# EnsembleTwo.net
KiCad netlist of a schematic drawn in EAGLE
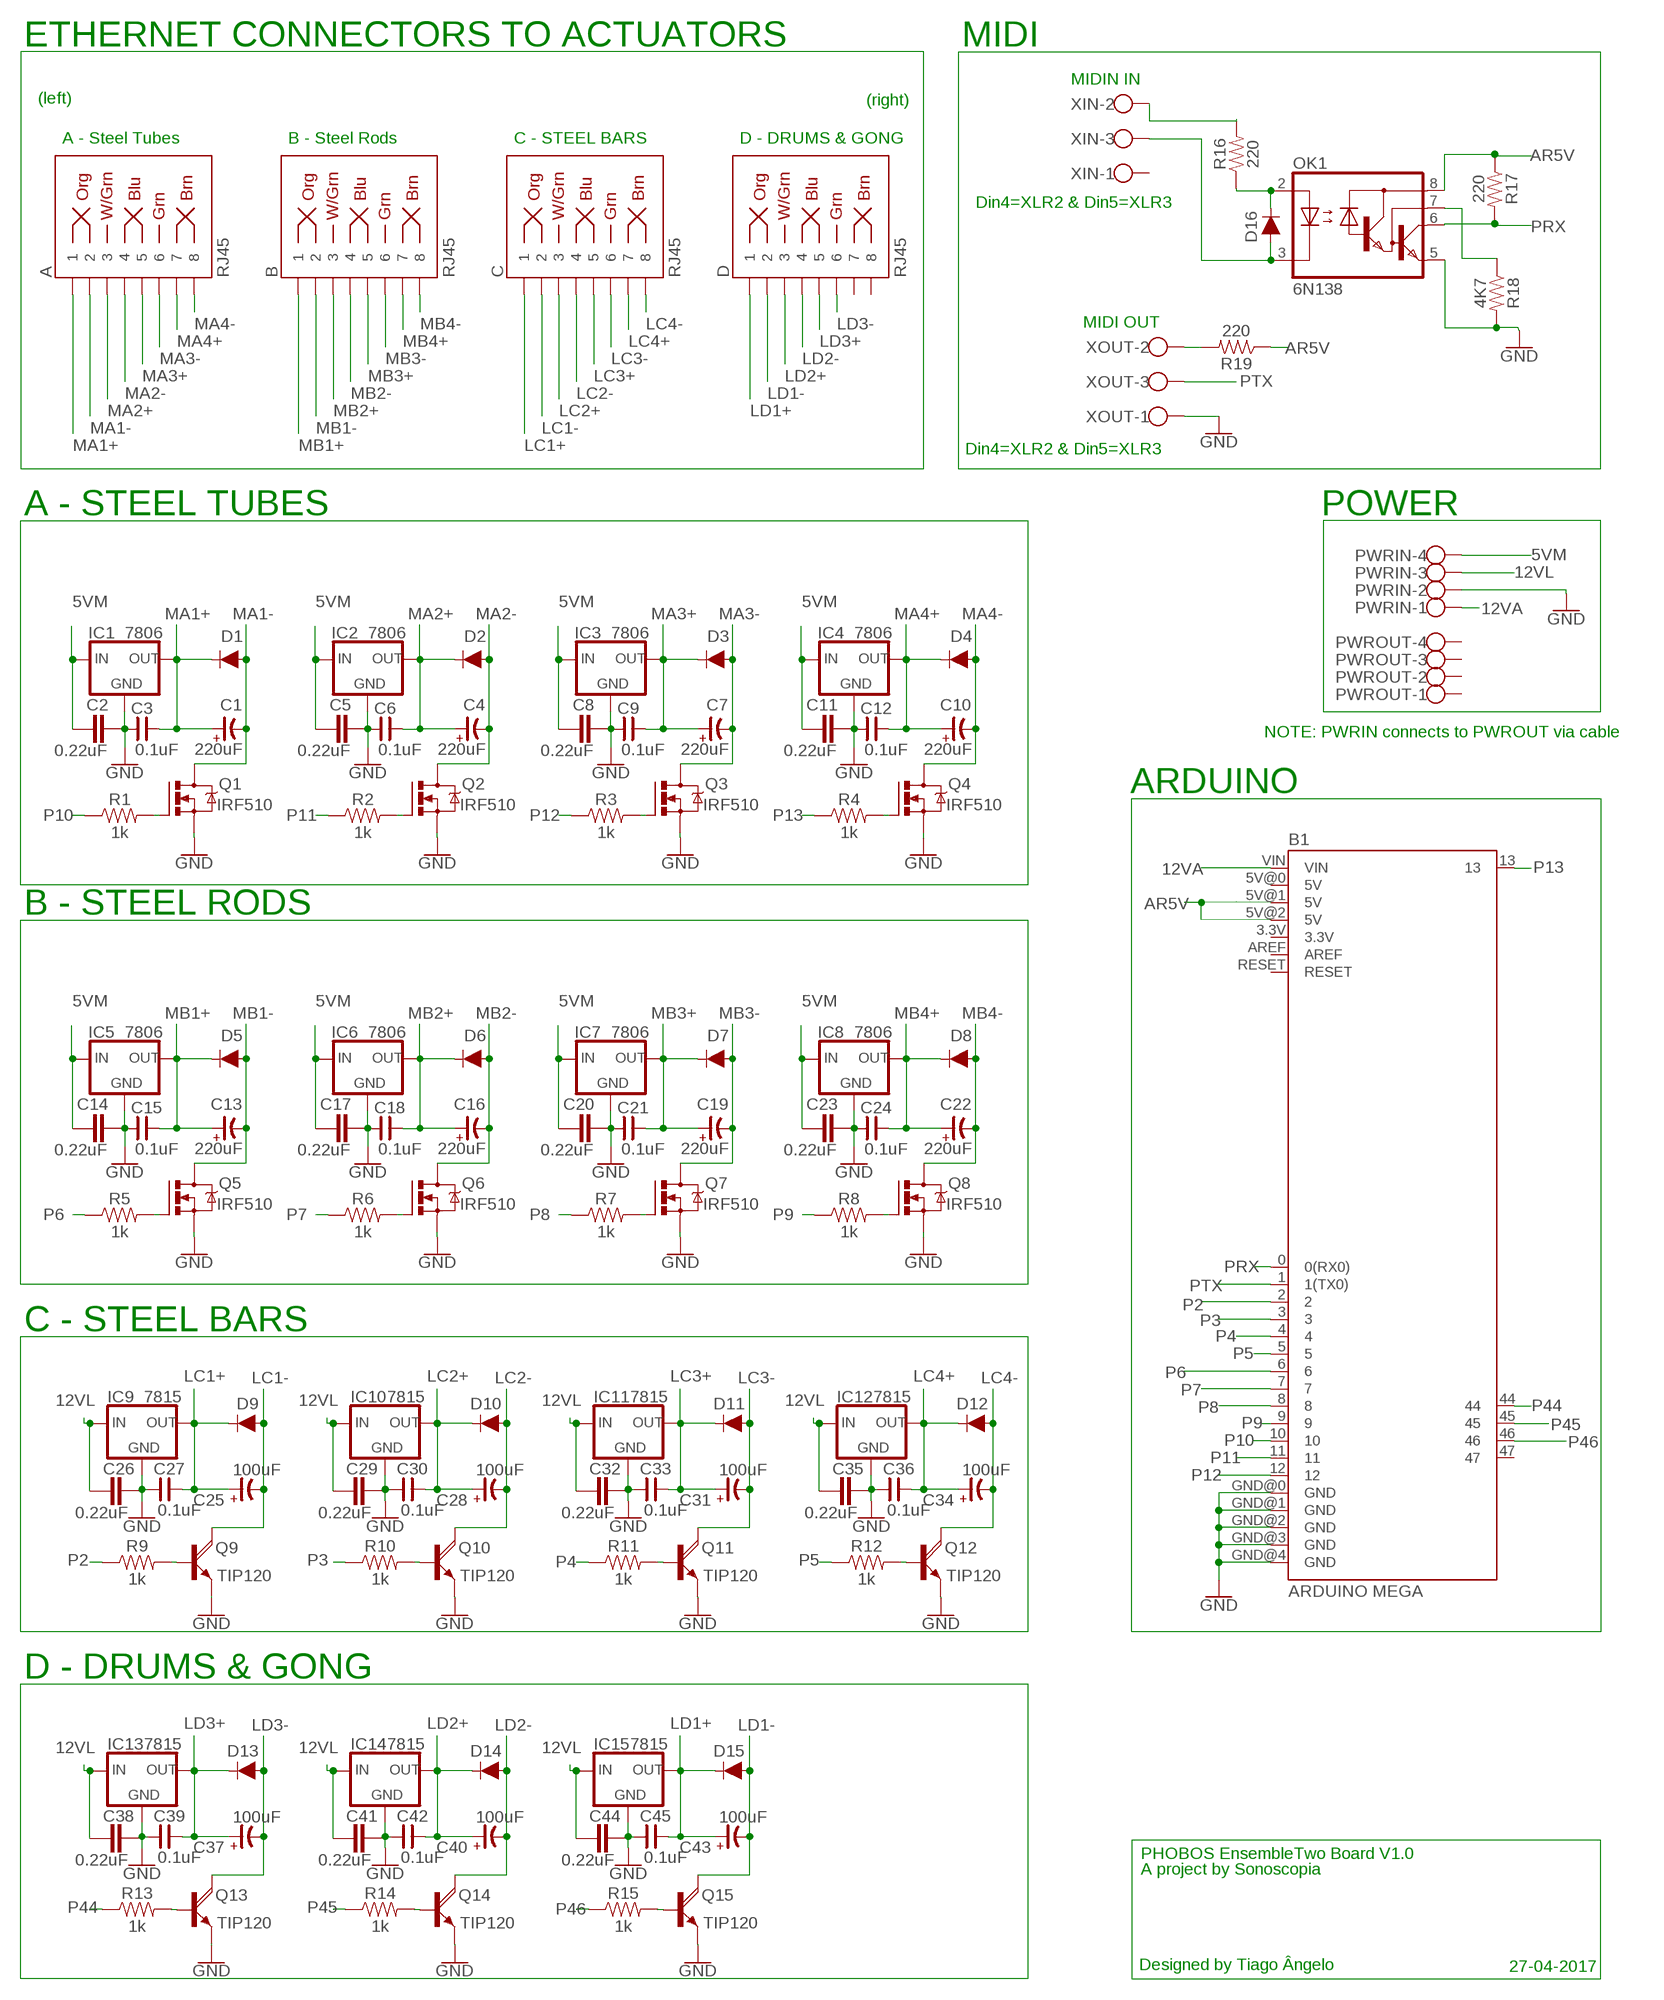
[diagram p0: schematic, sheet 1]

(export (version "E")
  (design (tool "Eeschema 10.0.6"))
  (components
    (comp (ref "A")
      (value "RJ45")
      (footprint "eagle-import:RJ45-8")
      (libsource (lib "eagle-import") (part "RJ45-8"))
    )
    (comp (ref "B")
      (value "RJ45")
      (footprint "eagle-import:RJ45-8")
      (libsource (lib "eagle-import") (part "RJ45-8"))
    )
    (comp (ref "B1")
      (value "ARDUINO MEGA")
      (footprint "eagle-import:ARDUINO_MEGA")
      (libsource (lib "eagle-import") (part "ARDUINO_MEGA_R3FULL"))
    )
    (comp (ref "C")
      (value "RJ45")
      (footprint "eagle-import:RJ45-8")
      (libsource (lib "eagle-import") (part "RJ45-8"))
    )
    (comp (ref "C1")
      (value "220uF")
      (footprint "eagle-import:E-035X080")
      (libsource (lib "eagle-import") (part "CP-E-035X080"))
    )
    (comp (ref "C2")
      (value "0.22uF")
      (footprint "eagle-import:C5B3")
      (libsource (lib "eagle-import") (part "C5/3"))
    )
    (comp (ref "C3")
      (value "0.1uF")
      (footprint "eagle-import:C025-050X025")
      (libsource (lib "eagle-import") (part "CNP-C025-050X025"))
    )
    (comp (ref "C4")
      (value "220uF")
      (footprint "eagle-import:E-035X080")
      (libsource (lib "eagle-import") (part "CP-E-035X080"))
    )
    (comp (ref "C5")
      (value "0.22uF")
      (footprint "eagle-import:C5B3")
      (libsource (lib "eagle-import") (part "C5/3"))
    )
    (comp (ref "C6")
      (value "0.1uF")
      (footprint "eagle-import:C025-050X025")
      (libsource (lib "eagle-import") (part "CNP-C025-050X025"))
    )
    (comp (ref "C7")
      (value "220uF")
      (footprint "eagle-import:E-035X080")
      (libsource (lib "eagle-import") (part "CP-E-035X080"))
    )
    (comp (ref "C8")
      (value "0.22uF")
      (footprint "eagle-import:C5B3")
      (libsource (lib "eagle-import") (part "C5/3"))
    )
    (comp (ref "C9")
      (value "0.1uF")
      (footprint "eagle-import:C025-050X025")
      (libsource (lib "eagle-import") (part "CNP-C025-050X025"))
    )
    (comp (ref "C10")
      (value "220uF")
      (footprint "eagle-import:E-035X080")
      (libsource (lib "eagle-import") (part "CP-E-035X080"))
    )
    (comp (ref "C11")
      (value "0.22uF")
      (footprint "eagle-import:C5B3")
      (libsource (lib "eagle-import") (part "C5/3"))
    )
    (comp (ref "C12")
      (value "0.1uF")
      (footprint "eagle-import:C025-050X025")
      (libsource (lib "eagle-import") (part "CNP-C025-050X025"))
    )
    (comp (ref "C13")
      (value "220uF")
      (footprint "eagle-import:E-035X080")
      (libsource (lib "eagle-import") (part "CP-E-035X080"))
    )
    (comp (ref "C14")
      (value "0.22uF")
      (footprint "eagle-import:C5B3")
      (libsource (lib "eagle-import") (part "C5/3"))
    )
    (comp (ref "C15")
      (value "0.1uF")
      (footprint "eagle-import:C025-050X025")
      (libsource (lib "eagle-import") (part "CNP-C025-050X025"))
    )
    (comp (ref "C16")
      (value "220uF")
      (footprint "eagle-import:E-035X080")
      (libsource (lib "eagle-import") (part "CP-E-035X080"))
    )
    (comp (ref "C17")
      (value "0.22uF")
      (footprint "eagle-import:C5B3")
      (libsource (lib "eagle-import") (part "C5/3"))
    )
    (comp (ref "C18")
      (value "0.1uF")
      (footprint "eagle-import:C025-050X025")
      (libsource (lib "eagle-import") (part "CNP-C025-050X025"))
    )
    (comp (ref "C19")
      (value "220uF")
      (footprint "eagle-import:E-035X080")
      (libsource (lib "eagle-import") (part "CP-E-035X080"))
    )
    (comp (ref "C20")
      (value "0.22uF")
      (footprint "eagle-import:C5B3")
      (libsource (lib "eagle-import") (part "C5/3"))
    )
    (comp (ref "C21")
      (value "0.1uF")
      (footprint "eagle-import:C025-050X025")
      (libsource (lib "eagle-import") (part "CNP-C025-050X025"))
    )
    (comp (ref "C22")
      (value "220uF")
      (footprint "eagle-import:E-035X080")
      (libsource (lib "eagle-import") (part "CP-E-035X080"))
    )
    (comp (ref "C23")
      (value "0.22uF")
      (footprint "eagle-import:C5B3")
      (libsource (lib "eagle-import") (part "C5/3"))
    )
    (comp (ref "C24")
      (value "0.1uF")
      (footprint "eagle-import:C025-050X025")
      (libsource (lib "eagle-import") (part "CNP-C025-050X025"))
    )
    (comp (ref "C25")
      (value "100uF")
      (footprint "eagle-import:E-020X050")
      (libsource (lib "eagle-import") (part "CP-E-020X050"))
    )
    (comp (ref "C26")
      (value "0.22uF")
      (footprint "eagle-import:C5B3")
      (libsource (lib "eagle-import") (part "C5/3"))
    )
    (comp (ref "C27")
      (value "0.1uF")
      (footprint "eagle-import:C025-050X025")
      (libsource (lib "eagle-import") (part "CNP-C025-050X025"))
    )
    (comp (ref "C28")
      (value "100uF")
      (footprint "eagle-import:E-020X050")
      (libsource (lib "eagle-import") (part "CP-E-020X050"))
    )
    (comp (ref "C29")
      (value "0.22uF")
      (footprint "eagle-import:C5B3")
      (libsource (lib "eagle-import") (part "C5/3"))
    )
    (comp (ref "C30")
      (value "0.1uF")
      (footprint "eagle-import:C025-050X025")
      (libsource (lib "eagle-import") (part "CNP-C025-050X025"))
    )
    (comp (ref "C31")
      (value "100uF")
      (footprint "eagle-import:E-020X050")
      (libsource (lib "eagle-import") (part "CP-E-020X050"))
    )
    (comp (ref "C32")
      (value "0.22uF")
      (footprint "eagle-import:C5B3")
      (libsource (lib "eagle-import") (part "C5/3"))
    )
    (comp (ref "C33")
      (value "0.1uF")
      (footprint "eagle-import:C025-050X025")
      (libsource (lib "eagle-import") (part "CNP-C025-050X025"))
    )
    (comp (ref "C34")
      (value "100uF")
      (footprint "eagle-import:E-020X050")
      (libsource (lib "eagle-import") (part "CP-E-020X050"))
    )
    (comp (ref "C35")
      (value "0.22uF")
      (footprint "eagle-import:C5B3")
      (libsource (lib "eagle-import") (part "C5/3"))
    )
    (comp (ref "C36")
      (value "0.1uF")
      (footprint "eagle-import:C025-050X025")
      (libsource (lib "eagle-import") (part "CNP-C025-050X025"))
    )
    (comp (ref "C37")
      (value "100uF")
      (footprint "eagle-import:E-020X050")
      (libsource (lib "eagle-import") (part "CP-E-020X050"))
    )
    (comp (ref "C38")
      (value "0.22uF")
      (footprint "eagle-import:C5B3")
      (libsource (lib "eagle-import") (part "C5/3"))
    )
    (comp (ref "C39")
      (value "0.1uF")
      (footprint "eagle-import:C025-050X025")
      (libsource (lib "eagle-import") (part "CNP-C025-050X025"))
    )
    (comp (ref "C40")
      (value "100uF")
      (footprint "eagle-import:E-020X050")
      (libsource (lib "eagle-import") (part "CP-E-020X050"))
    )
    (comp (ref "C41")
      (value "0.22uF")
      (footprint "eagle-import:C5B3")
      (libsource (lib "eagle-import") (part "C5/3"))
    )
    (comp (ref "C42")
      (value "0.1uF")
      (footprint "eagle-import:C025-050X025")
      (libsource (lib "eagle-import") (part "CNP-C025-050X025"))
    )
    (comp (ref "C43")
      (value "100uF")
      (footprint "eagle-import:E-020X050")
      (libsource (lib "eagle-import") (part "CP-E-020X050"))
    )
    (comp (ref "C44")
      (value "0.22uF")
      (footprint "eagle-import:C5B3")
      (libsource (lib "eagle-import") (part "C5/3"))
    )
    (comp (ref "C45")
      (value "0.1uF")
      (footprint "eagle-import:C025-050X025")
      (libsource (lib "eagle-import") (part "CNP-C025-050X025"))
    )
    (comp (ref "D")
      (value "RJ45")
      (footprint "eagle-import:RJ45-8")
      (libsource (lib "eagle-import") (part "RJ45-8"))
    )
    (comp (ref "D1")
      (value "1A/50V/1.1V")
      (footprint "eagle-import:DIODE-1N4001-KIT")
      (libsource (lib "eagle-import") (part "DIODE-KIT2"))
    )
    (comp (ref "D2")
      (value "1A/50V/1.1V")
      (footprint "eagle-import:DIODE-1N4001-KIT")
      (libsource (lib "eagle-import") (part "DIODE-KIT2"))
    )
    (comp (ref "D3")
      (value "1A/50V/1.1V")
      (footprint "eagle-import:DIODE-1N4001-KIT")
      (libsource (lib "eagle-import") (part "DIODE-KIT2"))
    )
    (comp (ref "D4")
      (value "1A/50V/1.1V")
      (footprint "eagle-import:DIODE-1N4001-KIT")
      (libsource (lib "eagle-import") (part "DIODE-KIT2"))
    )
    (comp (ref "D5")
      (value "1A/50V/1.1V")
      (footprint "eagle-import:DIODE-1N4001-KIT")
      (libsource (lib "eagle-import") (part "DIODE-KIT2"))
    )
    (comp (ref "D6")
      (value "1A/50V/1.1V")
      (footprint "eagle-import:DIODE-1N4001-KIT")
      (libsource (lib "eagle-import") (part "DIODE-KIT2"))
    )
    (comp (ref "D7")
      (value "1A/50V/1.1V")
      (footprint "eagle-import:DIODE-1N4001-KIT")
      (libsource (lib "eagle-import") (part "DIODE-KIT2"))
    )
    (comp (ref "D8")
      (value "1A/50V/1.1V")
      (footprint "eagle-import:DIODE-1N4001-KIT")
      (libsource (lib "eagle-import") (part "DIODE-KIT2"))
    )
    (comp (ref "D9")
      (value "1A/50V/1.1V")
      (footprint "eagle-import:DIODE-1N4001-KIT")
      (libsource (lib "eagle-import") (part "DIODE-KIT2"))
    )
    (comp (ref "D10")
      (value "1A/50V/1.1V")
      (footprint "eagle-import:DIODE-1N4001-KIT")
      (libsource (lib "eagle-import") (part "DIODE-KIT2"))
    )
    (comp (ref "D11")
      (value "1A/50V/1.1V")
      (footprint "eagle-import:DIODE-1N4001-KIT")
      (libsource (lib "eagle-import") (part "DIODE-KIT2"))
    )
    (comp (ref "D12")
      (value "1A/50V/1.1V")
      (footprint "eagle-import:DIODE-1N4001-KIT")
      (libsource (lib "eagle-import") (part "DIODE-KIT2"))
    )
    (comp (ref "D13")
      (value "1A/50V/1.1V")
      (footprint "eagle-import:DIODE-1N4001-KIT")
      (libsource (lib "eagle-import") (part "DIODE-KIT2"))
    )
    (comp (ref "D14")
      (value "1A/50V/1.1V")
      (footprint "eagle-import:DIODE-1N4001-KIT")
      (libsource (lib "eagle-import") (part "DIODE-KIT2"))
    )
    (comp (ref "D15")
      (value "1A/50V/1.1V")
      (footprint "eagle-import:DIODE-1N4001-KIT")
      (libsource (lib "eagle-import") (part "DIODE-KIT2"))
    )
    (comp (ref "D16")
      (value "200mA/100V/1V")
      (footprint "eagle-import:DIODE-1N4148")
      (libsource (lib "eagle-import") (part "DIODE-1N4148"))
    )
    (comp (ref "IC1")
      (value "7806")
      (footprint "eagle-import:78XXS")
      (libsource (lib "eagle-import") (part "78XXS"))
    )
    (comp (ref "IC2")
      (value "7806")
      (footprint "eagle-import:78XXS")
      (libsource (lib "eagle-import") (part "78XXS"))
    )
    (comp (ref "IC3")
      (value "7806")
      (footprint "eagle-import:78XXS")
      (libsource (lib "eagle-import") (part "78XXS"))
    )
    (comp (ref "IC4")
      (value "7806")
      (footprint "eagle-import:78XXS")
      (libsource (lib "eagle-import") (part "78XXS"))
    )
    (comp (ref "IC5")
      (value "7806")
      (footprint "eagle-import:78XXS")
      (libsource (lib "eagle-import") (part "78XXS"))
    )
    (comp (ref "IC6")
      (value "7806")
      (footprint "eagle-import:78XXS")
      (libsource (lib "eagle-import") (part "78XXS"))
    )
    (comp (ref "IC7")
      (value "7806")
      (footprint "eagle-import:78XXS")
      (libsource (lib "eagle-import") (part "78XXS"))
    )
    (comp (ref "IC8")
      (value "7806")
      (footprint "eagle-import:78XXS")
      (libsource (lib "eagle-import") (part "78XXS"))
    )
    (comp (ref "IC9")
      (value "7815")
      (footprint "eagle-import:78XXS")
      (libsource (lib "eagle-import") (part "78XXS"))
    )
    (comp (ref "IC10")
      (value "7815")
      (footprint "eagle-import:78XXS")
      (libsource (lib "eagle-import") (part "78XXS"))
    )
    (comp (ref "IC11")
      (value "7815")
      (footprint "eagle-import:78XXS")
      (libsource (lib "eagle-import") (part "78XXS"))
    )
    (comp (ref "IC12")
      (value "7815")
      (footprint "eagle-import:78XXS")
      (libsource (lib "eagle-import") (part "78XXS"))
    )
    (comp (ref "IC13")
      (value "7815")
      (footprint "eagle-import:78XXS")
      (libsource (lib "eagle-import") (part "78XXS"))
    )
    (comp (ref "IC14")
      (value "7815")
      (footprint "eagle-import:78XXS")
      (libsource (lib "eagle-import") (part "78XXS"))
    )
    (comp (ref "IC15")
      (value "7815")
      (footprint "eagle-import:78XXS")
      (libsource (lib "eagle-import") (part "78XXS"))
    )
    (comp (ref "OK1")
      (value "6N138")
      (footprint "eagle-import:DIL08")
      (fields (field (name "MF") "VISHAY/TELEFUNKEN"))
      (libsource (lib "eagle-import") (part "6N138"))
    )
    (comp (ref "PWRIN")
      (value "W237-4")
      (footprint "eagle-import:W237-4")
      (libsource (lib "eagle-import") (part "W237-4"))
    )
    (comp (ref "PWROUT")
      (value "W237-4")
      (footprint "eagle-import:W237-4")
      (libsource (lib "eagle-import") (part "W237-4"))
    )
    (comp (ref "Q1")
      (value "IRF510")
      (footprint "eagle-import:TO220BV")
      (libsource (lib "eagle-import") (part "IRF520"))
    )
    (comp (ref "Q2")
      (value "IRF510")
      (footprint "eagle-import:TO220BV")
      (libsource (lib "eagle-import") (part "IRF520"))
    )
    (comp (ref "Q3")
      (value "IRF510")
      (footprint "eagle-import:TO220BV")
      (libsource (lib "eagle-import") (part "IRF520"))
    )
    (comp (ref "Q4")
      (value "IRF510")
      (footprint "eagle-import:TO220BV")
      (libsource (lib "eagle-import") (part "IRF520"))
    )
    (comp (ref "Q5")
      (value "IRF510")
      (footprint "eagle-import:TO220BV")
      (libsource (lib "eagle-import") (part "IRF520"))
    )
    (comp (ref "Q6")
      (value "IRF510")
      (footprint "eagle-import:TO220BV")
      (libsource (lib "eagle-import") (part "IRF520"))
    )
    (comp (ref "Q7")
      (value "IRF510")
      (footprint "eagle-import:TO220BV")
      (libsource (lib "eagle-import") (part "IRF520"))
    )
    (comp (ref "Q8")
      (value "IRF510")
      (footprint "eagle-import:TO220BV")
      (libsource (lib "eagle-import") (part "IRF520"))
    )
    (comp (ref "Q9")
      (value "TIP120")
      (footprint "eagle-import:TO220AV")
      (libsource (lib "eagle-import") (part "TIP120V"))
    )
    (comp (ref "Q10")
      (value "TIP120")
      (footprint "eagle-import:TO220AV")
      (libsource (lib "eagle-import") (part "TIP120V"))
    )
    (comp (ref "Q11")
      (value "TIP120")
      (footprint "eagle-import:TO220AV")
      (libsource (lib "eagle-import") (part "TIP120V"))
    )
    (comp (ref "Q12")
      (value "TIP120")
      (footprint "eagle-import:TO220AV")
      (libsource (lib "eagle-import") (part "TIP120V"))
    )
    (comp (ref "Q13")
      (value "TIP120")
      (footprint "eagle-import:TO220AV")
      (libsource (lib "eagle-import") (part "TIP120V"))
    )
    (comp (ref "Q14")
      (value "TIP120")
      (footprint "eagle-import:TO220AV")
      (libsource (lib "eagle-import") (part "TIP120V"))
    )
    (comp (ref "Q15")
      (value "TIP120")
      (footprint "eagle-import:TO220AV")
      (libsource (lib "eagle-import") (part "TIP120V"))
    )
    (comp (ref "R1")
      (value "1k")
      (footprint "eagle-import:AXIAL-0.1")
      (libsource (lib "eagle-import") (part "1KOHM-VERT-1/4W-1%"))
    )
    (comp (ref "R2")
      (value "1k")
      (footprint "eagle-import:AXIAL-0.1")
      (libsource (lib "eagle-import") (part "1KOHM-VERT-1/4W-1%"))
    )
    (comp (ref "R3")
      (value "1k")
      (footprint "eagle-import:AXIAL-0.1")
      (libsource (lib "eagle-import") (part "1KOHM-VERT-1/4W-1%"))
    )
    (comp (ref "R4")
      (value "1k")
      (footprint "eagle-import:AXIAL-0.1")
      (libsource (lib "eagle-import") (part "1KOHM-VERT-1/4W-1%"))
    )
    (comp (ref "R5")
      (value "1k")
      (footprint "eagle-import:AXIAL-0.1")
      (libsource (lib "eagle-import") (part "1KOHM-VERT-1/4W-1%"))
    )
    (comp (ref "R6")
      (value "1k")
      (footprint "eagle-import:AXIAL-0.1")
      (libsource (lib "eagle-import") (part "1KOHM-VERT-1/4W-1%"))
    )
    (comp (ref "R7")
      (value "1k")
      (footprint "eagle-import:AXIAL-0.1")
      (libsource (lib "eagle-import") (part "1KOHM-VERT-1/4W-1%"))
    )
    (comp (ref "R8")
      (value "1k")
      (footprint "eagle-import:AXIAL-0.1")
      (libsource (lib "eagle-import") (part "1KOHM-VERT-1/4W-1%"))
    )
    (comp (ref "R9")
      (value "1k")
      (footprint "eagle-import:AXIAL-0.1")
      (libsource (lib "eagle-import") (part "1KOHM-VERT-1/4W-1%"))
    )
    (comp (ref "R10")
      (value "1k")
      (footprint "eagle-import:AXIAL-0.1")
      (libsource (lib "eagle-import") (part "1KOHM-VERT-1/4W-1%"))
    )
    (comp (ref "R11")
      (value "1k")
      (footprint "eagle-import:AXIAL-0.1")
      (libsource (lib "eagle-import") (part "1KOHM-VERT-1/4W-1%"))
    )
    (comp (ref "R12")
      (value "1k")
      (footprint "eagle-import:AXIAL-0.1")
      (libsource (lib "eagle-import") (part "1KOHM-VERT-1/4W-1%"))
    )
    (comp (ref "R13")
      (value "1k")
      (footprint "eagle-import:AXIAL-0.1")
      (libsource (lib "eagle-import") (part "1KOHM-VERT-1/4W-1%"))
    )
    (comp (ref "R14")
      (value "1k")
      (footprint "eagle-import:AXIAL-0.1")
      (libsource (lib "eagle-import") (part "1KOHM-VERT-1/4W-1%"))
    )
    (comp (ref "R15")
      (value "1k")
      (footprint "eagle-import:AXIAL-0.1")
      (libsource (lib "eagle-import") (part "1KOHM-VERT-1/4W-1%"))
    )
    (comp (ref "R16")
      (value "220")
      (footprint "eagle-import:AXIAL-0.3")
      (libsource (lib "eagle-import") (part "1KOHM-HORIZ-1/4W-5%"))
    )
    (comp (ref "R17")
      (value "220")
      (footprint "eagle-import:AXIAL-0.3")
      (libsource (lib "eagle-import") (part "1KOHM-HORIZ-1/4W-5%"))
    )
    (comp (ref "R18")
      (value "4K7")
      (footprint "eagle-import:AXIAL-0.3")
      (libsource (lib "eagle-import") (part "1KOHM-HORIZ-1/4W-5%"))
    )
    (comp (ref "R19")
      (value "220")
      (footprint "eagle-import:AXIAL-0.3")
      (libsource (lib "eagle-import") (part "1KOHM-HORIZ-1/4W-5%"))
    )
    (comp (ref "XIN")
      (value "W237-103")
      (footprint "eagle-import:W237-103")
      (fields (field (name "MPN") "237-103"))
      (libsource (lib "eagle-import") (part "W237-103"))
    )
    (comp (ref "XOUT")
      (value "W237-103")
      (footprint "eagle-import:W237-103")
      (fields (field (name "MPN") "237-103"))
      (libsource (lib "eagle-import") (part "W237-103"))
    )
  )
  (nets
    (net (code "1") (name "/5VM") (class "Default")
      (node (ref "C11") (pin "1") (pinfunction "1_1") (pintype "passive"))
      (node (ref "C14") (pin "1") (pinfunction "1_1") (pintype "passive"))
      (node (ref "C17") (pin "1") (pinfunction "1_1") (pintype "passive"))
      (node (ref "C2") (pin "1") (pinfunction "1_1") (pintype "passive"))
      (node (ref "C20") (pin "1") (pinfunction "1_1") (pintype "passive"))
      (node (ref "C23") (pin "1") (pinfunction "1_1") (pintype "passive"))
      (node (ref "C5") (pin "1") (pinfunction "1_1") (pintype "passive"))
      (node (ref "C8") (pin "1") (pinfunction "1_1") (pintype "passive"))
      (node (ref "IC1") (pin "IN") (pinfunction "IN_IN") (pintype "input"))
      (node (ref "IC2") (pin "IN") (pinfunction "IN_IN") (pintype "input"))
      (node (ref "IC3") (pin "IN") (pinfunction "IN_IN") (pintype "input"))
      (node (ref "IC4") (pin "IN") (pinfunction "IN_IN") (pintype "input"))
      (node (ref "IC5") (pin "IN") (pinfunction "IN_IN") (pintype "input"))
      (node (ref "IC6") (pin "IN") (pinfunction "IN_IN") (pintype "input"))
      (node (ref "IC7") (pin "IN") (pinfunction "IN_IN") (pintype "input"))
      (node (ref "IC8") (pin "IN") (pinfunction "IN_IN") (pintype "input"))
      (node (ref "PWRIN") (pin "4") (pinfunction "KL_4") (pintype "passive"))
    )
    (net (code "2") (name "/12VA") (class "Default")
      (node (ref "B1") (pin "VIN") (pinfunction "VIN_VIN") (pintype "bidirectional"))
      (node (ref "PWRIN") (pin "1") (pinfunction "KL_1") (pintype "passive"))
    )
    (net (code "3") (name "/12VL") (class "Default")
      (node (ref "C26") (pin "1") (pinfunction "1_1") (pintype "passive"))
      (node (ref "C29") (pin "1") (pinfunction "1_1") (pintype "passive"))
      (node (ref "C32") (pin "1") (pinfunction "1_1") (pintype "passive"))
      (node (ref "C35") (pin "1") (pinfunction "1_1") (pintype "passive"))
      (node (ref "C38") (pin "1") (pinfunction "1_1") (pintype "passive"))
      (node (ref "C41") (pin "1") (pinfunction "1_1") (pintype "passive"))
      (node (ref "C44") (pin "1") (pinfunction "1_1") (pintype "passive"))
      (node (ref "IC10") (pin "IN") (pinfunction "IN_IN") (pintype "input"))
      (node (ref "IC11") (pin "IN") (pinfunction "IN_IN") (pintype "input"))
      (node (ref "IC12") (pin "IN") (pinfunction "IN_IN") (pintype "input"))
      (node (ref "IC13") (pin "IN") (pinfunction "IN_IN") (pintype "input"))
      (node (ref "IC14") (pin "IN") (pinfunction "IN_IN") (pintype "input"))
      (node (ref "IC15") (pin "IN") (pinfunction "IN_IN") (pintype "input"))
      (node (ref "IC9") (pin "IN") (pinfunction "IN_IN") (pintype "input"))
      (node (ref "PWRIN") (pin "3") (pinfunction "KL_3") (pintype "passive"))
    )
    (net (code "4") (name "/AR5V") (class "Default")
      (node (ref "B1") (pin "5V@1") (pinfunction "5V_5V@1") (pintype "bidirectional"))
      (node (ref "B1") (pin "5V@2") (pinfunction "5V_5V@2") (pintype "bidirectional"))
      (node (ref "OK1") (pin "8") (pinfunction "VCC_8") (pintype "passive"))
      (node (ref "R17") (pin "P$1") (pinfunction "1_P$1") (pintype "passive"))
      (node (ref "R19") (pin "P$1") (pinfunction "1_P$1") (pintype "passive"))
    )
    (net (code "5") (name "/LC1+") (class "Default")
      (node (ref "C") (pin "1") (pinfunction "1_1") (pintype "bidirectional"))
      (node (ref "C25") (pin "+") (pinfunction "+_+") (pintype "passive"))
      (node (ref "C27") (pin "2") (pinfunction "2_2") (pintype "passive"))
      (node (ref "D9") (pin "C") (pinfunction "C_C") (pintype "passive"))
      (node (ref "IC9") (pin "OUT") (pinfunction "OUT_OUT") (pintype "passive"))
    )
    (net (code "6") (name "/LC1-") (class "Default")
      (node (ref "C") (pin "2") (pinfunction "2_2") (pintype "bidirectional"))
      (node (ref "C25") (pin "-") (pinfunction "-_-") (pintype "passive"))
      (node (ref "D9") (pin "A") (pinfunction "A_A") (pintype "passive"))
      (node (ref "Q9") (pin "C") (pinfunction "C_C") (pintype "passive"))
    )
    (net (code "7") (name "/LC2+") (class "Default")
      (node (ref "C") (pin "3") (pinfunction "3_3") (pintype "bidirectional"))
      (node (ref "C28") (pin "+") (pinfunction "+_+") (pintype "passive"))
      (node (ref "C30") (pin "2") (pinfunction "2_2") (pintype "passive"))
      (node (ref "D10") (pin "C") (pinfunction "C_C") (pintype "passive"))
      (node (ref "IC10") (pin "OUT") (pinfunction "OUT_OUT") (pintype "passive"))
    )
    (net (code "8") (name "/LC2-") (class "Default")
      (node (ref "C") (pin "4") (pinfunction "4_4") (pintype "bidirectional"))
      (node (ref "C28") (pin "-") (pinfunction "-_-") (pintype "passive"))
      (node (ref "D10") (pin "A") (pinfunction "A_A") (pintype "passive"))
      (node (ref "Q10") (pin "C") (pinfunction "C_C") (pintype "passive"))
    )
    (net (code "9") (name "/LC3+") (class "Default")
      (node (ref "C") (pin "5") (pinfunction "5_5") (pintype "bidirectional"))
      (node (ref "C31") (pin "+") (pinfunction "+_+") (pintype "passive"))
      (node (ref "C33") (pin "2") (pinfunction "2_2") (pintype "passive"))
      (node (ref "D11") (pin "C") (pinfunction "C_C") (pintype "passive"))
      (node (ref "IC11") (pin "OUT") (pinfunction "OUT_OUT") (pintype "passive"))
    )
    (net (code "10") (name "/LC3-") (class "Default")
      (node (ref "C") (pin "6") (pinfunction "6_6") (pintype "bidirectional"))
      (node (ref "C31") (pin "-") (pinfunction "-_-") (pintype "passive"))
      (node (ref "D11") (pin "A") (pinfunction "A_A") (pintype "passive"))
      (node (ref "Q11") (pin "C") (pinfunction "C_C") (pintype "passive"))
    )
    (net (code "11") (name "/LC4+") (class "Default")
      (node (ref "C") (pin "7") (pinfunction "7_7") (pintype "bidirectional"))
      (node (ref "C34") (pin "+") (pinfunction "+_+") (pintype "passive"))
      (node (ref "C36") (pin "2") (pinfunction "2_2") (pintype "passive"))
      (node (ref "D12") (pin "C") (pinfunction "C_C") (pintype "passive"))
      (node (ref "IC12") (pin "OUT") (pinfunction "OUT_OUT") (pintype "passive"))
    )
    (net (code "12") (name "/LC4-") (class "Default")
      (node (ref "C") (pin "8") (pinfunction "8_8") (pintype "bidirectional"))
      (node (ref "C34") (pin "-") (pinfunction "-_-") (pintype "passive"))
      (node (ref "D12") (pin "A") (pinfunction "A_A") (pintype "passive"))
      (node (ref "Q12") (pin "C") (pinfunction "C_C") (pintype "passive"))
    )
    (net (code "13") (name "/LD1+") (class "Default")
      (node (ref "C43") (pin "+") (pinfunction "+_+") (pintype "passive"))
      (node (ref "C45") (pin "2") (pinfunction "2_2") (pintype "passive"))
      (node (ref "D") (pin "1") (pinfunction "1_1") (pintype "bidirectional"))
      (node (ref "D15") (pin "C") (pinfunction "C_C") (pintype "passive"))
      (node (ref "IC15") (pin "OUT") (pinfunction "OUT_OUT") (pintype "passive"))
    )
    (net (code "14") (name "/LD1-") (class "Default")
      (node (ref "C43") (pin "-") (pinfunction "-_-") (pintype "passive"))
      (node (ref "D") (pin "2") (pinfunction "2_2") (pintype "bidirectional"))
      (node (ref "D15") (pin "A") (pinfunction "A_A") (pintype "passive"))
      (node (ref "Q15") (pin "C") (pinfunction "C_C") (pintype "passive"))
    )
    (net (code "15") (name "/LD2+") (class "Default")
      (node (ref "C40") (pin "+") (pinfunction "+_+") (pintype "passive"))
      (node (ref "C42") (pin "2") (pinfunction "2_2") (pintype "passive"))
      (node (ref "D") (pin "3") (pinfunction "3_3") (pintype "bidirectional"))
      (node (ref "D14") (pin "C") (pinfunction "C_C") (pintype "passive"))
      (node (ref "IC14") (pin "OUT") (pinfunction "OUT_OUT") (pintype "passive"))
    )
    (net (code "16") (name "/LD2-") (class "Default")
      (node (ref "C40") (pin "-") (pinfunction "-_-") (pintype "passive"))
      (node (ref "D") (pin "4") (pinfunction "4_4") (pintype "bidirectional"))
      (node (ref "D14") (pin "A") (pinfunction "A_A") (pintype "passive"))
      (node (ref "Q14") (pin "C") (pinfunction "C_C") (pintype "passive"))
    )
    (net (code "17") (name "/LD3+") (class "Default")
      (node (ref "C37") (pin "+") (pinfunction "+_+") (pintype "passive"))
      (node (ref "C39") (pin "2") (pinfunction "2_2") (pintype "passive"))
      (node (ref "D") (pin "5") (pinfunction "5_5") (pintype "bidirectional"))
      (node (ref "D13") (pin "C") (pinfunction "C_C") (pintype "passive"))
      (node (ref "IC13") (pin "OUT") (pinfunction "OUT_OUT") (pintype "passive"))
    )
    (net (code "18") (name "/LD3-") (class "Default")
      (node (ref "C37") (pin "-") (pinfunction "-_-") (pintype "passive"))
      (node (ref "D") (pin "6") (pinfunction "6_6") (pintype "bidirectional"))
      (node (ref "D13") (pin "A") (pinfunction "A_A") (pintype "passive"))
      (node (ref "Q13") (pin "C") (pinfunction "C_C") (pintype "passive"))
    )
    (net (code "19") (name "/MA1+") (class "Default")
      (node (ref "A") (pin "1") (pinfunction "1_1") (pintype "bidirectional"))
      (node (ref "C1") (pin "+") (pinfunction "+_+") (pintype "passive"))
      (node (ref "C3") (pin "2") (pinfunction "2_2") (pintype "passive"))
      (node (ref "D1") (pin "C") (pinfunction "C_C") (pintype "passive"))
      (node (ref "IC1") (pin "OUT") (pinfunction "OUT_OUT") (pintype "passive"))
    )
    (net (code "20") (name "/MA1-") (class "Default")
      (node (ref "A") (pin "2") (pinfunction "2_2") (pintype "bidirectional"))
      (node (ref "C1") (pin "-") (pinfunction "-_-") (pintype "passive"))
      (node (ref "D1") (pin "A") (pinfunction "A_A") (pintype "passive"))
      (node (ref "Q1") (pin "D") (pinfunction "D_D") (pintype "passive"))
    )
    (net (code "21") (name "/MA2+") (class "Default")
      (node (ref "A") (pin "3") (pinfunction "3_3") (pintype "bidirectional"))
      (node (ref "C4") (pin "+") (pinfunction "+_+") (pintype "passive"))
      (node (ref "C6") (pin "2") (pinfunction "2_2") (pintype "passive"))
      (node (ref "D2") (pin "C") (pinfunction "C_C") (pintype "passive"))
      (node (ref "IC2") (pin "OUT") (pinfunction "OUT_OUT") (pintype "passive"))
    )
    (net (code "22") (name "/MA2-") (class "Default")
      (node (ref "A") (pin "4") (pinfunction "4_4") (pintype "bidirectional"))
      (node (ref "C4") (pin "-") (pinfunction "-_-") (pintype "passive"))
      (node (ref "D2") (pin "A") (pinfunction "A_A") (pintype "passive"))
      (node (ref "Q2") (pin "D") (pinfunction "D_D") (pintype "passive"))
    )
    (net (code "23") (name "/MA3+") (class "Default")
      (node (ref "A") (pin "5") (pinfunction "5_5") (pintype "bidirectional"))
      (node (ref "C7") (pin "+") (pinfunction "+_+") (pintype "passive"))
      (node (ref "C9") (pin "2") (pinfunction "2_2") (pintype "passive"))
      (node (ref "D3") (pin "C") (pinfunction "C_C") (pintype "passive"))
      (node (ref "IC3") (pin "OUT") (pinfunction "OUT_OUT") (pintype "passive"))
    )
    (net (code "24") (name "/MA3-") (class "Default")
      (node (ref "A") (pin "6") (pinfunction "6_6") (pintype "bidirectional"))
      (node (ref "C7") (pin "-") (pinfunction "-_-") (pintype "passive"))
      (node (ref "D3") (pin "A") (pinfunction "A_A") (pintype "passive"))
      (node (ref "Q3") (pin "D") (pinfunction "D_D") (pintype "passive"))
    )
    (net (code "25") (name "/MA4+") (class "Default")
      (node (ref "A") (pin "7") (pinfunction "7_7") (pintype "bidirectional"))
      (node (ref "C10") (pin "+") (pinfunction "+_+") (pintype "passive"))
      (node (ref "C12") (pin "2") (pinfunction "2_2") (pintype "passive"))
      (node (ref "D4") (pin "C") (pinfunction "C_C") (pintype "passive"))
      (node (ref "IC4") (pin "OUT") (pinfunction "OUT_OUT") (pintype "passive"))
    )
    (net (code "26") (name "/MA4-") (class "Default")
      (node (ref "A") (pin "8") (pinfunction "8_8") (pintype "bidirectional"))
      (node (ref "C10") (pin "-") (pinfunction "-_-") (pintype "passive"))
      (node (ref "D4") (pin "A") (pinfunction "A_A") (pintype "passive"))
      (node (ref "Q4") (pin "D") (pinfunction "D_D") (pintype "passive"))
    )
    (net (code "27") (name "/MB1+") (class "Default")
      (node (ref "B") (pin "1") (pinfunction "1_1") (pintype "bidirectional"))
      (node (ref "C13") (pin "+") (pinfunction "+_+") (pintype "passive"))
      (node (ref "C15") (pin "2") (pinfunction "2_2") (pintype "passive"))
      (node (ref "D5") (pin "C") (pinfunction "C_C") (pintype "passive"))
      (node (ref "IC5") (pin "OUT") (pinfunction "OUT_OUT") (pintype "passive"))
    )
    (net (code "28") (name "/MB1-") (class "Default")
      (node (ref "B") (pin "2") (pinfunction "2_2") (pintype "bidirectional"))
      (node (ref "C13") (pin "-") (pinfunction "-_-") (pintype "passive"))
      (node (ref "D5") (pin "A") (pinfunction "A_A") (pintype "passive"))
      (node (ref "Q5") (pin "D") (pinfunction "D_D") (pintype "passive"))
    )
    (net (code "29") (name "/MB2+") (class "Default")
      (node (ref "B") (pin "3") (pinfunction "3_3") (pintype "bidirectional"))
      (node (ref "C16") (pin "+") (pinfunction "+_+") (pintype "passive"))
      (node (ref "C18") (pin "2") (pinfunction "2_2") (pintype "passive"))
      (node (ref "D6") (pin "C") (pinfunction "C_C") (pintype "passive"))
      (node (ref "IC6") (pin "OUT") (pinfunction "OUT_OUT") (pintype "passive"))
    )
    (net (code "30") (name "/MB2-") (class "Default")
      (node (ref "B") (pin "4") (pinfunction "4_4") (pintype "bidirectional"))
      (node (ref "C16") (pin "-") (pinfunction "-_-") (pintype "passive"))
      (node (ref "D6") (pin "A") (pinfunction "A_A") (pintype "passive"))
      (node (ref "Q6") (pin "D") (pinfunction "D_D") (pintype "passive"))
    )
    (net (code "31") (name "/MB3+") (class "Default")
      (node (ref "B") (pin "5") (pinfunction "5_5") (pintype "bidirectional"))
      (node (ref "C19") (pin "+") (pinfunction "+_+") (pintype "passive"))
      (node (ref "C21") (pin "2") (pinfunction "2_2") (pintype "passive"))
      (node (ref "D7") (pin "C") (pinfunction "C_C") (pintype "passive"))
      (node (ref "IC7") (pin "OUT") (pinfunction "OUT_OUT") (pintype "passive"))
    )
    (net (code "32") (name "/MB3-") (class "Default")
      (node (ref "B") (pin "6") (pinfunction "6_6") (pintype "bidirectional"))
      (node (ref "C19") (pin "-") (pinfunction "-_-") (pintype "passive"))
      (node (ref "D7") (pin "A") (pinfunction "A_A") (pintype "passive"))
      (node (ref "Q7") (pin "D") (pinfunction "D_D") (pintype "passive"))
    )
    (net (code "33") (name "/MB4+") (class "Default")
      (node (ref "B") (pin "7") (pinfunction "7_7") (pintype "bidirectional"))
      (node (ref "C22") (pin "+") (pinfunction "+_+") (pintype "passive"))
      (node (ref "C24") (pin "2") (pinfunction "2_2") (pintype "passive"))
      (node (ref "D8") (pin "C") (pinfunction "C_C") (pintype "passive"))
      (node (ref "IC8") (pin "OUT") (pinfunction "OUT_OUT") (pintype "passive"))
    )
    (net (code "34") (name "/MB4-") (class "Default")
      (node (ref "B") (pin "8") (pinfunction "8_8") (pintype "bidirectional"))
      (node (ref "C22") (pin "-") (pinfunction "-_-") (pintype "passive"))
      (node (ref "D8") (pin "A") (pinfunction "A_A") (pintype "passive"))
      (node (ref "Q8") (pin "D") (pinfunction "D_D") (pintype "passive"))
    )
    (net (code "35") (name "/P2") (class "Default")
      (node (ref "B1") (pin "2") (pinfunction "2_2") (pintype "bidirectional"))
      (node (ref "R9") (pin "P$1") (pinfunction "1_P$1") (pintype "passive"))
    )
    (net (code "36") (name "/P3") (class "Default")
      (node (ref "B1") (pin "3") (pinfunction "3_3") (pintype "bidirectional"))
      (node (ref "R10") (pin "P$1") (pinfunction "1_P$1") (pintype "passive"))
    )
    (net (code "37") (name "/P4") (class "Default")
      (node (ref "B1") (pin "4") (pinfunction "4_4") (pintype "bidirectional"))
      (node (ref "R11") (pin "P$1") (pinfunction "1_P$1") (pintype "passive"))
    )
    (net (code "38") (name "/P5") (class "Default")
      (node (ref "B1") (pin "5") (pinfunction "5_5") (pintype "bidirectional"))
      (node (ref "R12") (pin "P$1") (pinfunction "1_P$1") (pintype "passive"))
    )
    (net (code "39") (name "/P6") (class "Default")
      (node (ref "B1") (pin "6") (pinfunction "6_6") (pintype "bidirectional"))
      (node (ref "R5") (pin "P$1") (pinfunction "1_P$1") (pintype "passive"))
    )
    (net (code "40") (name "/P7") (class "Default")
      (node (ref "B1") (pin "7") (pinfunction "7_7") (pintype "bidirectional"))
      (node (ref "R6") (pin "P$1") (pinfunction "1_P$1") (pintype "passive"))
    )
    (net (code "41") (name "/P8") (class "Default")
      (node (ref "B1") (pin "8") (pinfunction "8_8") (pintype "bidirectional"))
      (node (ref "R7") (pin "P$1") (pinfunction "1_P$1") (pintype "passive"))
    )
    (net (code "42") (name "/P9") (class "Default")
      (node (ref "B1") (pin "9") (pinfunction "9_9") (pintype "bidirectional"))
      (node (ref "R8") (pin "P$1") (pinfunction "1_P$1") (pintype "passive"))
    )
    (net (code "43") (name "/P10") (class "Default")
      (node (ref "B1") (pin "10") (pinfunction "10_10") (pintype "bidirectional"))
      (node (ref "R1") (pin "P$1") (pinfunction "1_P$1") (pintype "passive"))
    )
    (net (code "44") (name "/P11") (class "Default")
      (node (ref "B1") (pin "11") (pinfunction "11_11") (pintype "bidirectional"))
      (node (ref "R2") (pin "P$1") (pinfunction "1_P$1") (pintype "passive"))
    )
    (net (code "45") (name "/P12") (class "Default")
      (node (ref "B1") (pin "12") (pinfunction "12_12") (pintype "bidirectional"))
      (node (ref "R3") (pin "P$1") (pinfunction "1_P$1") (pintype "passive"))
    )
    (net (code "46") (name "/P13") (class "Default")
      (node (ref "B1") (pin "13") (pinfunction "13_13") (pintype "bidirectional"))
      (node (ref "R4") (pin "P$1") (pinfunction "1_P$1") (pintype "passive"))
    )
    (net (code "47") (name "/P44") (class "Default")
      (node (ref "B1") (pin "44") (pinfunction "44_44") (pintype "bidirectional"))
      (node (ref "R13") (pin "P$1") (pinfunction "1_P$1") (pintype "passive"))
    )
    (net (code "48") (name "/P45") (class "Default")
      (node (ref "B1") (pin "45") (pinfunction "45_45") (pintype "bidirectional"))
      (node (ref "R14") (pin "P$1") (pinfunction "1_P$1") (pintype "passive"))
    )
    (net (code "49") (name "/P46") (class "Default")
      (node (ref "B1") (pin "46") (pinfunction "46_46") (pintype "bidirectional"))
      (node (ref "R15") (pin "P$1") (pinfunction "1_P$1") (pintype "passive"))
    )
    (net (code "50") (name "/PRX") (class "Default")
      (node (ref "B1") (pin "0") (pinfunction "0(RX0)_0") (pintype "bidirectional"))
      (node (ref "OK1") (pin "6") (pinfunction "VO_6") (pintype "passive"))
      (node (ref "R17") (pin "P$2") (pinfunction "2_P$2") (pintype "passive"))
    )
    (net (code "51") (name "/PTX") (class "Default")
      (node (ref "B1") (pin "1") (pinfunction "1(TX0)_1") (pintype "bidirectional"))
      (node (ref "XOUT") (pin "3") (pinfunction "KL_3") (pintype "passive"))
    )
    (net (code "52") (name "GND") (class "Default")
      (node (ref "B1") (pin "GND@0") (pinfunction "GND_GND@0") (pintype "bidirectional"))
      (node (ref "B1") (pin "GND@1") (pinfunction "GND_GND@1") (pintype "bidirectional"))
      (node (ref "B1") (pin "GND@2") (pinfunction "GND_GND@2") (pintype "bidirectional"))
      (node (ref "B1") (pin "GND@3") (pinfunction "GND_GND@3") (pintype "bidirectional"))
      (node (ref "B1") (pin "GND@4") (pinfunction "GND_GND@4") (pintype "bidirectional"))
      (node (ref "C11") (pin "2") (pinfunction "2_2") (pintype "passive"))
      (node (ref "C12") (pin "1") (pinfunction "1_1") (pintype "passive"))
      (node (ref "C14") (pin "2") (pinfunction "2_2") (pintype "passive"))
      (node (ref "C15") (pin "1") (pinfunction "1_1") (pintype "passive"))
      (node (ref "C17") (pin "2") (pinfunction "2_2") (pintype "passive"))
      (node (ref "C18") (pin "1") (pinfunction "1_1") (pintype "passive"))
      (node (ref "C2") (pin "2") (pinfunction "2_2") (pintype "passive"))
      (node (ref "C20") (pin "2") (pinfunction "2_2") (pintype "passive"))
      (node (ref "C21") (pin "1") (pinfunction "1_1") (pintype "passive"))
      (node (ref "C23") (pin "2") (pinfunction "2_2") (pintype "passive"))
      (node (ref "C24") (pin "1") (pinfunction "1_1") (pintype "passive"))
      (node (ref "C26") (pin "2") (pinfunction "2_2") (pintype "passive"))
      (node (ref "C27") (pin "1") (pinfunction "1_1") (pintype "passive"))
      (node (ref "C29") (pin "2") (pinfunction "2_2") (pintype "passive"))
      (node (ref "C3") (pin "1") (pinfunction "1_1") (pintype "passive"))
      (node (ref "C30") (pin "1") (pinfunction "1_1") (pintype "passive"))
      (node (ref "C32") (pin "2") (pinfunction "2_2") (pintype "passive"))
      (node (ref "C33") (pin "1") (pinfunction "1_1") (pintype "passive"))
      (node (ref "C35") (pin "2") (pinfunction "2_2") (pintype "passive"))
      (node (ref "C36") (pin "1") (pinfunction "1_1") (pintype "passive"))
      (node (ref "C38") (pin "2") (pinfunction "2_2") (pintype "passive"))
      (node (ref "C39") (pin "1") (pinfunction "1_1") (pintype "passive"))
      (node (ref "C41") (pin "2") (pinfunction "2_2") (pintype "passive"))
      (node (ref "C42") (pin "1") (pinfunction "1_1") (pintype "passive"))
      (node (ref "C44") (pin "2") (pinfunction "2_2") (pintype "passive"))
      (node (ref "C45") (pin "1") (pinfunction "1_1") (pintype "passive"))
      (node (ref "C5") (pin "2") (pinfunction "2_2") (pintype "passive"))
      (node (ref "C6") (pin "1") (pinfunction "1_1") (pintype "passive"))
      (node (ref "C8") (pin "2") (pinfunction "2_2") (pintype "passive"))
      (node (ref "C9") (pin "1") (pinfunction "1_1") (pintype "passive"))
      (node (ref "IC1") (pin "GND") (pinfunction "GND_GND") (pintype "input"))
      (node (ref "IC10") (pin "GND") (pinfunction "GND_GND") (pintype "input"))
      (node (ref "IC11") (pin "GND") (pinfunction "GND_GND") (pintype "input"))
      (node (ref "IC12") (pin "GND") (pinfunction "GND_GND") (pintype "input"))
      (node (ref "IC13") (pin "GND") (pinfunction "GND_GND") (pintype "input"))
      (node (ref "IC14") (pin "GND") (pinfunction "GND_GND") (pintype "input"))
      (node (ref "IC15") (pin "GND") (pinfunction "GND_GND") (pintype "input"))
      (node (ref "IC2") (pin "GND") (pinfunction "GND_GND") (pintype "input"))
      (node (ref "IC3") (pin "GND") (pinfunction "GND_GND") (pintype "input"))
      (node (ref "IC4") (pin "GND") (pinfunction "GND_GND") (pintype "input"))
      (node (ref "IC5") (pin "GND") (pinfunction "GND_GND") (pintype "input"))
      (node (ref "IC6") (pin "GND") (pinfunction "GND_GND") (pintype "input"))
      (node (ref "IC7") (pin "GND") (pinfunction "GND_GND") (pintype "input"))
      (node (ref "IC8") (pin "GND") (pinfunction "GND_GND") (pintype "input"))
      (node (ref "IC9") (pin "GND") (pinfunction "GND_GND") (pintype "input"))
      (node (ref "OK1") (pin "5") (pinfunction "GND_5") (pintype "passive"))
      (node (ref "PWRIN") (pin "2") (pinfunction "KL_2") (pintype "passive"))
      (node (ref "Q1") (pin "S") (pinfunction "S_S") (pintype "passive"))
      (node (ref "Q10") (pin "E") (pinfunction "E_E") (pintype "passive"))
      (node (ref "Q11") (pin "E") (pinfunction "E_E") (pintype "passive"))
      (node (ref "Q12") (pin "E") (pinfunction "E_E") (pintype "passive"))
      (node (ref "Q13") (pin "E") (pinfunction "E_E") (pintype "passive"))
      (node (ref "Q14") (pin "E") (pinfunction "E_E") (pintype "passive"))
      (node (ref "Q15") (pin "E") (pinfunction "E_E") (pintype "passive"))
      (node (ref "Q2") (pin "S") (pinfunction "S_S") (pintype "passive"))
      (node (ref "Q3") (pin "S") (pinfunction "S_S") (pintype "passive"))
      (node (ref "Q4") (pin "S") (pinfunction "S_S") (pintype "passive"))
      (node (ref "Q5") (pin "S") (pinfunction "S_S") (pintype "passive"))
      (node (ref "Q6") (pin "S") (pinfunction "S_S") (pintype "passive"))
      (node (ref "Q7") (pin "S") (pinfunction "S_S") (pintype "passive"))
      (node (ref "Q8") (pin "S") (pinfunction "S_S") (pintype "passive"))
      (node (ref "Q9") (pin "E") (pinfunction "E_E") (pintype "passive"))
      (node (ref "R18") (pin "P$2") (pinfunction "2_P$2") (pintype "passive"))
      (node (ref "XOUT") (pin "1") (pinfunction "KL_1") (pintype "passive"))
    )
    (net (code "53") (name "Net-(OK1-A)") (class "Default")
      (node (ref "D16") (pin "C") (pinfunction "C_C") (pintype "passive"))
      (node (ref "OK1") (pin "2") (pinfunction "A_2") (pintype "passive"))
      (node (ref "R16") (pin "P$1") (pinfunction "1_P$1") (pintype "passive"))
    )
    (net (code "54") (name "Net-(OK1-C)") (class "Default")
      (node (ref "D16") (pin "A") (pinfunction "A_A") (pintype "passive"))
      (node (ref "OK1") (pin "3") (pinfunction "C_3") (pintype "passive"))
      (node (ref "XIN") (pin "3") (pinfunction "KL_3") (pintype "passive"))
    )
    (net (code "55") (name "Net-(OK1-VB)") (class "Default")
      (node (ref "OK1") (pin "7") (pinfunction "VB_7") (pintype "passive"))
      (node (ref "R18") (pin "P$1") (pinfunction "1_P$1") (pintype "passive"))
    )
    (net (code "56") (name "Net-(R1-2)") (class "Default")
      (node (ref "Q1") (pin "G") (pinfunction "G_G") (pintype "passive"))
      (node (ref "R1") (pin "P$2") (pinfunction "2_P$2") (pintype "passive"))
    )
    (net (code "57") (name "Net-(R2-2)") (class "Default")
      (node (ref "Q2") (pin "G") (pinfunction "G_G") (pintype "passive"))
      (node (ref "R2") (pin "P$2") (pinfunction "2_P$2") (pintype "passive"))
    )
    (net (code "58") (name "Net-(R3-2)") (class "Default")
      (node (ref "Q3") (pin "G") (pinfunction "G_G") (pintype "passive"))
      (node (ref "R3") (pin "P$2") (pinfunction "2_P$2") (pintype "passive"))
    )
    (net (code "59") (name "Net-(R4-2)") (class "Default")
      (node (ref "Q4") (pin "G") (pinfunction "G_G") (pintype "passive"))
      (node (ref "R4") (pin "P$2") (pinfunction "2_P$2") (pintype "passive"))
    )
    (net (code "60") (name "Net-(R5-2)") (class "Default")
      (node (ref "Q5") (pin "G") (pinfunction "G_G") (pintype "passive"))
      (node (ref "R5") (pin "P$2") (pinfunction "2_P$2") (pintype "passive"))
    )
    (net (code "61") (name "Net-(R6-2)") (class "Default")
      (node (ref "Q6") (pin "G") (pinfunction "G_G") (pintype "passive"))
      (node (ref "R6") (pin "P$2") (pinfunction "2_P$2") (pintype "passive"))
    )
    (net (code "62") (name "Net-(R7-2)") (class "Default")
      (node (ref "Q7") (pin "G") (pinfunction "G_G") (pintype "passive"))
      (node (ref "R7") (pin "P$2") (pinfunction "2_P$2") (pintype "passive"))
    )
    (net (code "63") (name "Net-(R8-2)") (class "Default")
      (node (ref "Q8") (pin "G") (pinfunction "G_G") (pintype "passive"))
      (node (ref "R8") (pin "P$2") (pinfunction "2_P$2") (pintype "passive"))
    )
    (net (code "64") (name "Net-(R9-2)") (class "Default")
      (node (ref "Q9") (pin "B") (pinfunction "B_B") (pintype "passive"))
      (node (ref "R9") (pin "P$2") (pinfunction "2_P$2") (pintype "passive"))
    )
    (net (code "65") (name "Net-(R10-2)") (class "Default")
      (node (ref "Q10") (pin "B") (pinfunction "B_B") (pintype "passive"))
      (node (ref "R10") (pin "P$2") (pinfunction "2_P$2") (pintype "passive"))
    )
    (net (code "66") (name "Net-(R11-2)") (class "Default")
      (node (ref "Q11") (pin "B") (pinfunction "B_B") (pintype "passive"))
      (node (ref "R11") (pin "P$2") (pinfunction "2_P$2") (pintype "passive"))
    )
    (net (code "67") (name "Net-(R12-2)") (class "Default")
      (node (ref "Q12") (pin "B") (pinfunction "B_B") (pintype "passive"))
      (node (ref "R12") (pin "P$2") (pinfunction "2_P$2") (pintype "passive"))
    )
    (net (code "68") (name "Net-(R13-2)") (class "Default")
      (node (ref "Q13") (pin "B") (pinfunction "B_B") (pintype "passive"))
      (node (ref "R13") (pin "P$2") (pinfunction "2_P$2") (pintype "passive"))
    )
    (net (code "69") (name "Net-(R14-2)") (class "Default")
      (node (ref "Q14") (pin "B") (pinfunction "B_B") (pintype "passive"))
      (node (ref "R14") (pin "P$2") (pinfunction "2_P$2") (pintype "passive"))
    )
    (net (code "70") (name "Net-(R15-2)") (class "Default")
      (node (ref "Q15") (pin "B") (pinfunction "B_B") (pintype "passive"))
      (node (ref "R15") (pin "P$2") (pinfunction "2_P$2") (pintype "passive"))
    )
    (net (code "71") (name "Net-(R16-2)") (class "Default")
      (node (ref "R16") (pin "P$2") (pinfunction "2_P$2") (pintype "passive"))
      (node (ref "XIN") (pin "2") (pinfunction "KL_2") (pintype "passive"))
    )
    (net (code "72") (name "Net-(R19-2)") (class "Default")
      (node (ref "R19") (pin "P$2") (pinfunction "2_P$2") (pintype "passive"))
      (node (ref "XOUT") (pin "2") (pinfunction "KL_2") (pintype "passive"))
    )
    (net (code "73") (name "unconnected-(B1-5V-Pad5V@0)") (class "Default")
      (node (ref "B1") (pin "5V@0") (pinfunction "5V_5V@0") (pintype "bidirectional"))
    )
    (net (code "74") (name "unconnected-(B1-Pad3.3V)") (class "Default")
      (node (ref "B1") (pin "3.3V") (pinfunction "3.3V_3.3V") (pintype "bidirectional"))
    )
    (net (code "75") (name "unconnected-(B1-Pad47)") (class "Default")
      (node (ref "B1") (pin "47") (pinfunction "47_47") (pintype "bidirectional"))
    )
    (net (code "76") (name "unconnected-(B1-PadAREF)") (class "Default")
      (node (ref "B1") (pin "AREF") (pinfunction "AREF_AREF") (pintype "bidirectional"))
    )
    (net (code "77") (name "unconnected-(B1-PadRESET)") (class "Default")
      (node (ref "B1") (pin "RESET") (pinfunction "RESET_RESET") (pintype "bidirectional"))
    )
    (net (code "78") (name "unconnected-(D-Pad7)") (class "Default")
      (node (ref "D") (pin "7") (pinfunction "7_7") (pintype "bidirectional"))
    )
    (net (code "79") (name "unconnected-(D-Pad8)") (class "Default")
      (node (ref "D") (pin "8") (pinfunction "8_8") (pintype "bidirectional"))
    )
    (net (code "80") (name "unconnected-(PWROUTA-KL-Pad1)") (class "Default")
      (node (ref "PWROUT") (pin "1") (pinfunction "KL_1") (pintype "passive"))
    )
    (net (code "81") (name "unconnected-(PWROUTB-KL-Pad2)") (class "Default")
      (node (ref "PWROUT") (pin "2") (pinfunction "KL_2") (pintype "passive"))
    )
    (net (code "82") (name "unconnected-(PWROUTC-KL-Pad3)") (class "Default")
      (node (ref "PWROUT") (pin "3") (pinfunction "KL_3") (pintype "passive"))
    )
    (net (code "83") (name "unconnected-(PWROUTD-KL-Pad4)") (class "Default")
      (node (ref "PWROUT") (pin "4") (pinfunction "KL_4") (pintype "passive"))
    )
    (net (code "84") (name "unconnected-(XINA-KL-Pad1)") (class "Default")
      (node (ref "XIN") (pin "1") (pinfunction "KL_1") (pintype "passive"))
    )
  )
)
